# Frontend.net
KiCad netlist of a schematic drawn in Altium Designer
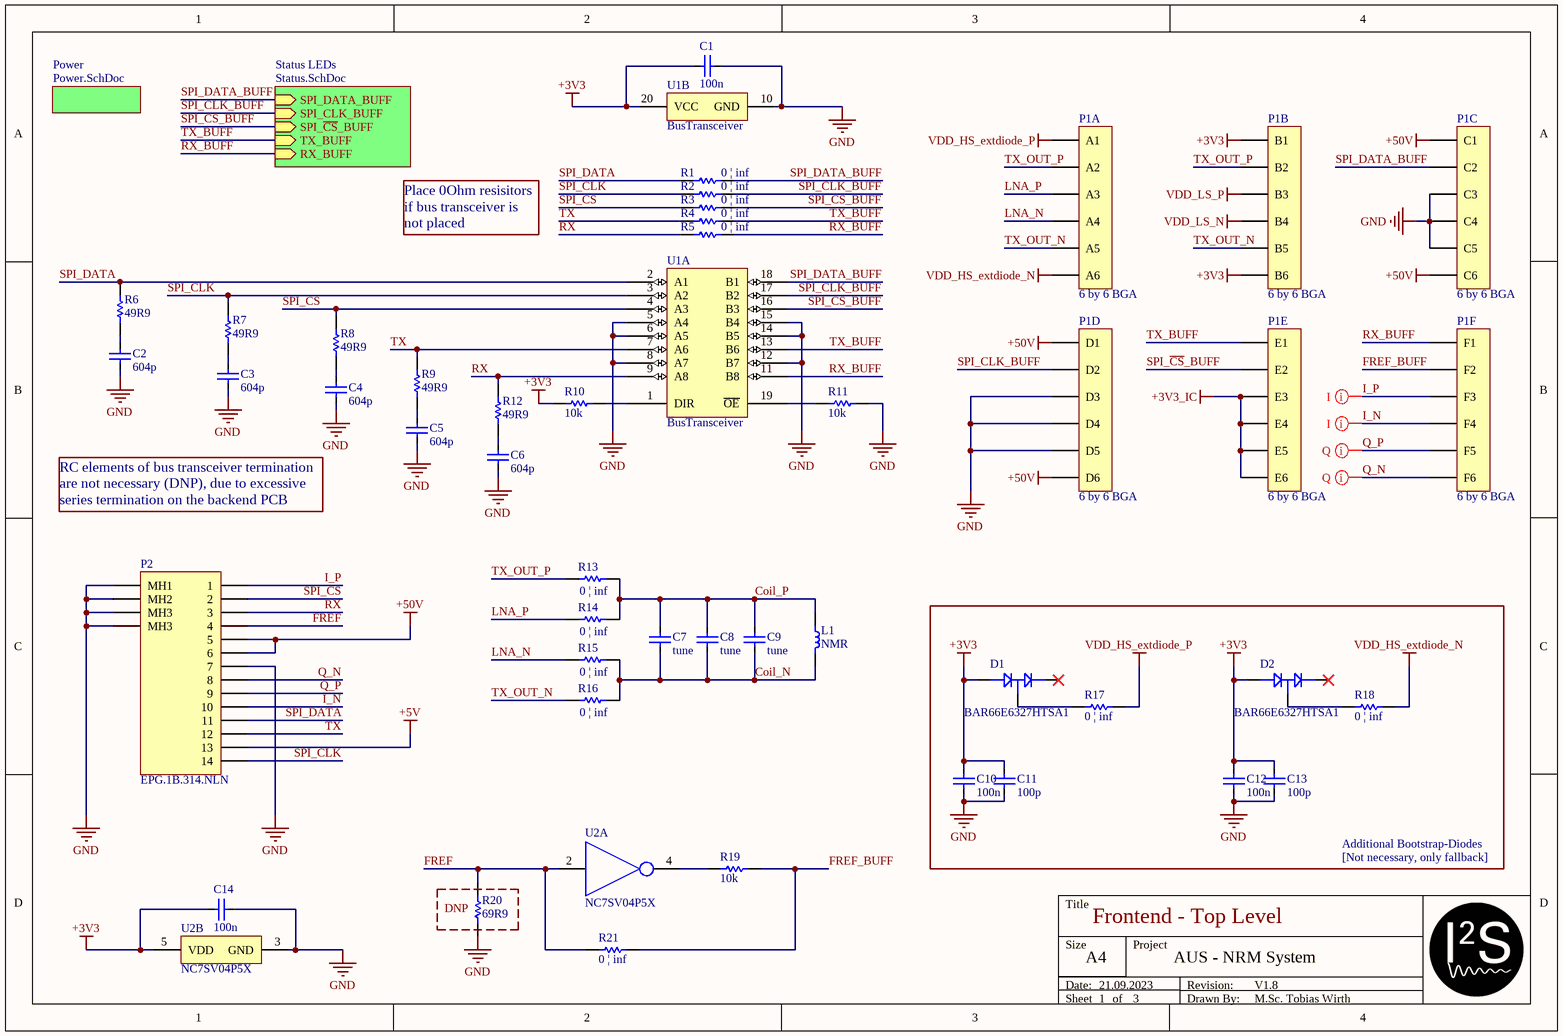
[diagram p0: Frontend.SchDoc]

(export (version "E")
  (design (tool "Eeschema 10.0.6"))
  (components
    (comp (ref "C1") (value "100n") (footprint "CAP_0402") (libsource (lib "IIS-Lib_TW") (part "Cap")))
    (comp (ref "C2") (value "604p") (footprint "CAP_0402") (libsource (lib "IIS-Lib_TW") (part "Cap")))
    (comp (ref "C3") (value "604p") (footprint "CAP_0402") (libsource (lib "IIS-Lib_TW") (part "Cap")))
    (comp (ref "C4") (value "604p") (footprint "CAP_0402") (libsource (lib "IIS-Lib_TW") (part "Cap")))
    (comp (ref "C5") (value "604p") (footprint "CAP_0402") (libsource (lib "IIS-Lib_TW") (part "Cap")))
    (comp (ref "C6") (value "604p") (footprint "CAP_0402") (libsource (lib "IIS-Lib_TW") (part "Cap")))
    (comp (ref "C7") (value "tune") (footprint "CAP_1206") (libsource (lib "IIS-Lib_TW") (part "Cap")))
    (comp (ref "C8") (value "tune") (footprint "CAP_0805") (libsource (lib "IIS-Lib_TW") (part "Cap")))
    (comp (ref "C9") (value "tune") (footprint "CAP_0603") (libsource (lib "IIS-Lib_TW") (part "Cap")))
    (comp (ref "C10") (value "100n") (footprint "CAP_0402") (libsource (lib "IIS-Lib_TW") (part "Cap")))
    (comp (ref "C11") (value "100p") (footprint "CAP_0402") (libsource (lib "IIS-Lib_TW") (part "Cap")))
    (comp (ref "C12") (value "100n") (footprint "CAP_0402") (libsource (lib "IIS-Lib_TW") (part "Cap")))
    (comp (ref "C13") (value "100p") (footprint "CAP_0402") (libsource (lib "IIS-Lib_TW") (part "Cap")))
    (comp (ref "C14") (value "100n") (footprint "CAP_0402") (libsource (lib "IIS-Lib_TW") (part "Cap")))
    (comp (ref "D1")
      (value "BAR66E6327HTSA1")
      (footprint "SOT23")
      (description "SMP1320-075LF (SC-70)\r\nBAV99 (SOT23)")
      (libsource (lib "IIS-Lib_TW") (part "Diode_series"))
    )
    (comp (ref "D2")
      (value "BAR66E6327HTSA1")
      (footprint "SOT23")
      (description "SMP1320-075LF (SC-70)\r\nBAV99 (SOT23)")
      (libsource (lib "IIS-Lib_TW") (part "Diode_series"))
    )
    (comp (ref "L1") (value "NMR") (footprint "NMR-Coil-Pads") (libsource (lib "IIS-Lib_TW") (part "Ind")))
    (comp (ref "P1")
      (value "6 by 6 BGA")
      (footprint "BGA36C230P6X6_1500X1500X190 - Interposer")
      (libsource (lib "IIS-Lib_TW") (part "BGA_6x6"))
    )
    (comp (ref "P2")
      (value "EPG.1B.314.NLN")
      (footprint "EPG.1B.314.NLN")
      (libsource (lib "IIS-Lib_TW") (part "EPG.1B.314.NLN"))
    )
    (comp (ref "R1") (value "0 ¦ inf") (footprint "RES_0402") (libsource (lib "IIS-Lib_TW") (part "Res")))
    (comp (ref "R2") (value "0 ¦ inf") (footprint "RES_0402") (libsource (lib "IIS-Lib_TW") (part "Res")))
    (comp (ref "R3") (value "0 ¦ inf") (footprint "RES_0402") (libsource (lib "IIS-Lib_TW") (part "Res")))
    (comp (ref "R4") (value "0 ¦ inf") (footprint "RES_0402") (libsource (lib "IIS-Lib_TW") (part "Res")))
    (comp (ref "R5") (value "0 ¦ inf") (footprint "RES_0402") (libsource (lib "IIS-Lib_TW") (part "Res")))
    (comp (ref "R6") (value "49R9") (footprint "RES_0402") (libsource (lib "IIS-Lib_TW") (part "Res")))
    (comp (ref "R7") (value "49R9") (footprint "RES_0402") (libsource (lib "IIS-Lib_TW") (part "Res")))
    (comp (ref "R8") (value "49R9") (footprint "RES_0402") (libsource (lib "IIS-Lib_TW") (part "Res")))
    (comp (ref "R9") (value "49R9") (footprint "RES_0402") (libsource (lib "IIS-Lib_TW") (part "Res")))
    (comp (ref "R10") (value "10k") (footprint "RES_0402") (libsource (lib "IIS-Lib_TW") (part "Res")))
    (comp (ref "R11") (value "10k") (footprint "RES_0402") (libsource (lib "IIS-Lib_TW") (part "Res")))
    (comp (ref "R12") (value "49R9") (footprint "RES_0402") (libsource (lib "IIS-Lib_TW") (part "Res")))
    (comp (ref "R13") (value "0 ¦ inf") (footprint "RES_0402") (libsource (lib "IIS-Lib_TW") (part "Res")))
    (comp (ref "R14") (value "0 ¦ inf") (footprint "RES_0402") (libsource (lib "IIS-Lib_TW") (part "Res")))
    (comp (ref "R15") (value "0 ¦ inf") (footprint "RES_0402") (libsource (lib "IIS-Lib_TW") (part "Res")))
    (comp (ref "R16") (value "0 ¦ inf") (footprint "RES_0402") (libsource (lib "IIS-Lib_TW") (part "Res")))
    (comp (ref "R17") (value "0 ¦ inf") (footprint "RES_0402") (libsource (lib "IIS-Lib_TW") (part "Res")))
    (comp (ref "R18") (value "0 ¦ inf") (footprint "RES_0402") (libsource (lib "IIS-Lib_TW") (part "Res")))
    (comp (ref "R19") (value "10k") (footprint "RES_0402") (libsource (lib "IIS-Lib_TW") (part "Res")))
    (comp (ref "R20") (value "69R9") (footprint "RES_0603") (libsource (lib "IIS-Lib_TW") (part "Res")))
    (comp (ref "R21") (value "0 ¦ inf") (footprint "RES_0402") (libsource (lib "IIS-Lib_TW") (part "Res")))
    (comp (ref "U1")
      (value "BusTransceiver")
      (footprint "TSSOP-20")
      (libsource (lib "") (part "74LVC245A_1"))
    )
    (comp (ref "U2")
      (value "NC7SV04P5X")
      (footprint "SOT23-65P210X110-5N")
      (libsource (lib "IIS-Lib_TW") (part "NC7SV04P5X"))
    )
  )
  (nets
    (net (code "1") (name "+3V3") (class "Default")
      (node (ref "C1") (pin "1") (pinfunction "1_1") (pintype "passive"))
      (node (ref "C10") (pin "1") (pinfunction "1_1") (pintype "passive"))
      (node (ref "C11") (pin "1") (pinfunction "1_1") (pintype "passive"))
      (node (ref "C12") (pin "1") (pinfunction "1_1") (pintype "passive"))
      (node (ref "C13") (pin "1") (pinfunction "1_1") (pintype "passive"))
      (node (ref "C14") (pin "1") (pinfunction "1_1") (pintype "passive"))
      (node (ref "D1") (pin "1") (pinfunction "1_1") (pintype "passive"))
      (node (ref "D2") (pin "1") (pinfunction "1_1") (pintype "passive"))
      (node (ref "P1") (pin "B1") (pinfunction "B1_B1") (pintype "passive"))
      (node (ref "P1") (pin "B6") (pinfunction "B6_B6") (pintype "passive"))
      (node (ref "R10") (pin "1") (pinfunction "1_1") (pintype "passive"))
      (node (ref "U1") (pin "20") (pinfunction "VCC_20") (pintype "passive"))
      (node (ref "U2") (pin "5") (pinfunction "VDD_5") (pintype "passive"))
    )
    (net (code "2") (name "+3V3_IC") (class "Default")
      (node (ref "P1") (pin "E3") (pinfunction "E3_E3") (pintype "passive"))
      (node (ref "P1") (pin "E4") (pinfunction "E4_E4") (pintype "passive"))
      (node (ref "P1") (pin "E5") (pinfunction "E5_E5") (pintype "passive"))
      (node (ref "P1") (pin "E6") (pinfunction "E6_E6") (pintype "passive"))
    )
    (net (code "3") (name "+5V") (class "Default")
      (node (ref "P2") (pin "13") (pinfunction "13_13") (pintype "passive"))
    )
    (net (code "4") (name "+50V") (class "Default")
      (node (ref "P1") (pin "C1") (pinfunction "C1_C1") (pintype "passive"))
      (node (ref "P1") (pin "C6") (pinfunction "C6_C6") (pintype "passive"))
      (node (ref "P1") (pin "D1") (pinfunction "D1_D1") (pintype "passive"))
      (node (ref "P1") (pin "D6") (pinfunction "D6_D6") (pintype "passive"))
      (node (ref "P2") (pin "5") (pinfunction "5_5") (pintype "passive"))
      (node (ref "P2") (pin "6") (pinfunction "6_6") (pintype "passive"))
    )
    (net (code "5") (name "/Coil_N") (class "Default")
      (node (ref "C7") (pin "2") (pinfunction "2_2") (pintype "passive"))
      (node (ref "C8") (pin "2") (pinfunction "2_2") (pintype "passive"))
      (node (ref "C9") (pin "2") (pinfunction "2_2") (pintype "passive"))
      (node (ref "L1") (pin "2") (pinfunction "2_2") (pintype "passive"))
      (node (ref "R15") (pin "1") (pinfunction "1_1") (pintype "passive"))
      (node (ref "R16") (pin "1") (pinfunction "1_1") (pintype "passive"))
    )
    (net (code "6") (name "/Coil_P") (class "Default")
      (node (ref "C7") (pin "1") (pinfunction "1_1") (pintype "passive"))
      (node (ref "C8") (pin "1") (pinfunction "1_1") (pintype "passive"))
      (node (ref "C9") (pin "1") (pinfunction "1_1") (pintype "passive"))
      (node (ref "L1") (pin "1") (pinfunction "1_1") (pintype "passive"))
      (node (ref "R13") (pin "1") (pinfunction "1_1") (pintype "passive"))
      (node (ref "R14") (pin "1") (pinfunction "1_1") (pintype "passive"))
    )
    (net (code "7") (name "/FREF") (class "Default")
      (node (ref "P2") (pin "4") (pinfunction "4_4") (pintype "passive"))
      (node (ref "R20") (pin "2") (pinfunction "2_2") (pintype "passive"))
      (node (ref "R21") (pin "2") (pinfunction "2_2") (pintype "passive"))
      (node (ref "U2") (pin "2") (pinfunction "2_2") (pintype "passive"))
    )
    (net (code "8") (name "/FREF_BUFF") (class "Default")
      (node (ref "P1") (pin "F2") (pinfunction "F2_F2") (pintype "passive"))
      (node (ref "R19") (pin "2") (pinfunction "2_2") (pintype "passive"))
      (node (ref "R21") (pin "1") (pinfunction "1_1") (pintype "passive"))
    )
    (net (code "9") (name "/I_N") (class "Default")
      (node (ref "P1") (pin "F4") (pinfunction "F4_F4") (pintype "passive"))
      (node (ref "P2") (pin "10") (pinfunction "10_10") (pintype "passive"))
    )
    (net (code "10") (name "/I_P") (class "Default")
      (node (ref "P1") (pin "F3") (pinfunction "F3_F3") (pintype "passive"))
      (node (ref "P2") (pin "1") (pinfunction "1_1") (pintype "passive"))
    )
    (net (code "11") (name "/LNA_N") (class "Default")
      (node (ref "P1") (pin "A4") (pinfunction "A4_A4") (pintype "passive"))
      (node (ref "R15") (pin "2") (pinfunction "2_2") (pintype "passive"))
    )
    (net (code "12") (name "/LNA_P") (class "Default")
      (node (ref "P1") (pin "A3") (pinfunction "A3_A3") (pintype "passive"))
      (node (ref "R14") (pin "2") (pinfunction "2_2") (pintype "passive"))
    )
    (net (code "13") (name "/Q_N") (class "Default")
      (node (ref "P1") (pin "F6") (pinfunction "F6_F6") (pintype "passive"))
      (node (ref "P2") (pin "8") (pinfunction "8_8") (pintype "passive"))
    )
    (net (code "14") (name "/Q_P") (class "Default")
      (node (ref "P1") (pin "F5") (pinfunction "F5_F5") (pintype "passive"))
      (node (ref "P2") (pin "9") (pinfunction "9_9") (pintype "passive"))
    )
    (net (code "15") (name "/RX") (class "Default")
      (node (ref "P2") (pin "3") (pinfunction "3_3") (pintype "passive"))
      (node (ref "R12") (pin "2") (pinfunction "2_2") (pintype "passive"))
      (node (ref "R5") (pin "1") (pinfunction "1_1") (pintype "passive"))
      (node (ref "U1") (pin "9") (pinfunction "A8_9") (pintype "bidirectional"))
    )
    (net (code "16") (name "/RX_BUFF") (class "Default")
      (node (ref "P1") (pin "F1") (pinfunction "F1_F1") (pintype "passive"))
      (node (ref "R5") (pin "2") (pinfunction "2_2") (pintype "passive"))
      (node (ref "U1") (pin "11") (pinfunction "B8_11") (pintype "bidirectional"))
    )
    (net (code "17") (name "/SPI_CLK") (class "Default")
      (node (ref "P2") (pin "14") (pinfunction "14_14") (pintype "passive"))
      (node (ref "R2") (pin "1") (pinfunction "1_1") (pintype "passive"))
      (node (ref "R7") (pin "2") (pinfunction "2_2") (pintype "passive"))
      (node (ref "U1") (pin "3") (pinfunction "A2_3") (pintype "bidirectional"))
    )
    (net (code "18") (name "/SPI_CLK_BUFF") (class "Default")
      (node (ref "P1") (pin "D2") (pinfunction "D2_D2") (pintype "passive"))
      (node (ref "R2") (pin "2") (pinfunction "2_2") (pintype "passive"))
      (node (ref "U1") (pin "17") (pinfunction "B2_17") (pintype "bidirectional"))
    )
    (net (code "19") (name "/SPI_DATA") (class "Default")
      (node (ref "P2") (pin "11") (pinfunction "11_11") (pintype "passive"))
      (node (ref "R1") (pin "1") (pinfunction "1_1") (pintype "passive"))
      (node (ref "R6") (pin "2") (pinfunction "2_2") (pintype "passive"))
      (node (ref "U1") (pin "2") (pinfunction "A1_2") (pintype "bidirectional"))
    )
    (net (code "20") (name "/SPI_DATA_BUFF") (class "Default")
      (node (ref "P1") (pin "C2") (pinfunction "C2_C2") (pintype "passive"))
      (node (ref "R1") (pin "2") (pinfunction "2_2") (pintype "passive"))
      (node (ref "U1") (pin "18") (pinfunction "B1_18") (pintype "bidirectional"))
    )
    (net (code "21") (name "/SPI_~{CS}") (class "Default")
      (node (ref "P2") (pin "2") (pinfunction "2_2") (pintype "passive"))
      (node (ref "R3") (pin "1") (pinfunction "1_1") (pintype "passive"))
      (node (ref "R8") (pin "2") (pinfunction "2_2") (pintype "passive"))
      (node (ref "U1") (pin "4") (pinfunction "A3_4") (pintype "bidirectional"))
    )
    (net (code "22") (name "/SPI_~{CS}_BUFF") (class "Default")
      (node (ref "P1") (pin "E2") (pinfunction "E2_E2") (pintype "passive"))
      (node (ref "R3") (pin "2") (pinfunction "2_2") (pintype "passive"))
      (node (ref "U1") (pin "16") (pinfunction "B3_16") (pintype "bidirectional"))
    )
    (net (code "23") (name "/TX") (class "Default")
      (node (ref "P2") (pin "12") (pinfunction "12_12") (pintype "passive"))
      (node (ref "R4") (pin "1") (pinfunction "1_1") (pintype "passive"))
      (node (ref "R9") (pin "2") (pinfunction "2_2") (pintype "passive"))
      (node (ref "U1") (pin "7") (pinfunction "A6_7") (pintype "bidirectional"))
    )
    (net (code "24") (name "/TX_BUFF") (class "Default")
      (node (ref "P1") (pin "E1") (pinfunction "E1_E1") (pintype "passive"))
      (node (ref "R4") (pin "2") (pinfunction "2_2") (pintype "passive"))
      (node (ref "U1") (pin "13") (pinfunction "B6_13") (pintype "bidirectional"))
    )
    (net (code "25") (name "/TX_OUT_N") (class "Default")
      (node (ref "P1") (pin "A5") (pinfunction "A5_A5") (pintype "passive"))
      (node (ref "P1") (pin "B5") (pinfunction "B5_B5") (pintype "passive"))
      (node (ref "R16") (pin "2") (pinfunction "2_2") (pintype "passive"))
    )
    (net (code "26") (name "/TX_OUT_P") (class "Default")
      (node (ref "P1") (pin "A2") (pinfunction "A2_A2") (pintype "passive"))
      (node (ref "P1") (pin "B2") (pinfunction "B2_B2") (pintype "passive"))
      (node (ref "R13") (pin "2") (pinfunction "2_2") (pintype "passive"))
    )
    (net (code "27") (name "GND") (class "Default")
      (node (ref "C1") (pin "2") (pinfunction "2_2") (pintype "passive"))
      (node (ref "C10") (pin "2") (pinfunction "2_2") (pintype "passive"))
      (node (ref "C11") (pin "2") (pinfunction "2_2") (pintype "passive"))
      (node (ref "C12") (pin "2") (pinfunction "2_2") (pintype "passive"))
      (node (ref "C13") (pin "2") (pinfunction "2_2") (pintype "passive"))
      (node (ref "C14") (pin "2") (pinfunction "2_2") (pintype "passive"))
      (node (ref "C2") (pin "2") (pinfunction "2_2") (pintype "passive"))
      (node (ref "C3") (pin "2") (pinfunction "2_2") (pintype "passive"))
      (node (ref "C4") (pin "2") (pinfunction "2_2") (pintype "passive"))
      (node (ref "C5") (pin "2") (pinfunction "2_2") (pintype "passive"))
      (node (ref "C6") (pin "2") (pinfunction "2_2") (pintype "passive"))
      (node (ref "P1") (pin "C3") (pinfunction "C3_C3") (pintype "passive"))
      (node (ref "P1") (pin "C4") (pinfunction "C4_C4") (pintype "passive"))
      (node (ref "P1") (pin "C5") (pinfunction "C5_C5") (pintype "passive"))
      (node (ref "P1") (pin "D3") (pinfunction "D3_D3") (pintype "passive"))
      (node (ref "P1") (pin "D4") (pinfunction "D4_D4") (pintype "passive"))
      (node (ref "P1") (pin "D5") (pinfunction "D5_D5") (pintype "passive"))
      (node (ref "P2") (pin "15") (pinfunction "MH1_15") (pintype "passive"))
      (node (ref "P2") (pin "16") (pinfunction "MH2_16") (pintype "passive"))
      (node (ref "P2") (pin "17") (pinfunction "MH3_17") (pintype "passive"))
      (node (ref "P2") (pin "18") (pinfunction "MH3_18") (pintype "passive"))
      (node (ref "P2") (pin "7") (pinfunction "7_7") (pintype "passive"))
      (node (ref "R11") (pin "2") (pinfunction "2_2") (pintype "passive"))
      (node (ref "R20") (pin "1") (pinfunction "1_1") (pintype "passive"))
      (node (ref "U1") (pin "10") (pinfunction "GND_10") (pintype "passive"))
      (node (ref "U1") (pin "12") (pinfunction "B7_12") (pintype "bidirectional"))
      (node (ref "U1") (pin "14") (pinfunction "B5_14") (pintype "bidirectional"))
      (node (ref "U1") (pin "15") (pinfunction "B4_15") (pintype "bidirectional"))
      (node (ref "U1") (pin "5") (pinfunction "A4_5") (pintype "bidirectional"))
      (node (ref "U1") (pin "6") (pinfunction "A5_6") (pintype "bidirectional"))
      (node (ref "U1") (pin "8") (pinfunction "A7_8") (pintype "bidirectional"))
      (node (ref "U2") (pin "3") (pinfunction "GND_3") (pintype "passive"))
    )
    (net (code "28") (name "Net-(C2-Pad1)") (class "Default")
      (node (ref "C2") (pin "1") (pinfunction "1_1") (pintype "passive"))
      (node (ref "R6") (pin "1") (pinfunction "1_1") (pintype "passive"))
    )
    (net (code "29") (name "Net-(C3-Pad1)") (class "Default")
      (node (ref "C3") (pin "1") (pinfunction "1_1") (pintype "passive"))
      (node (ref "R7") (pin "1") (pinfunction "1_1") (pintype "passive"))
    )
    (net (code "30") (name "Net-(C4-Pad1)") (class "Default")
      (node (ref "C4") (pin "1") (pinfunction "1_1") (pintype "passive"))
      (node (ref "R8") (pin "1") (pinfunction "1_1") (pintype "passive"))
    )
    (net (code "31") (name "Net-(C5-Pad1)") (class "Default")
      (node (ref "C5") (pin "1") (pinfunction "1_1") (pintype "passive"))
      (node (ref "R9") (pin "1") (pinfunction "1_1") (pintype "passive"))
    )
    (net (code "32") (name "Net-(C6-Pad1)") (class "Default")
      (node (ref "C6") (pin "1") (pinfunction "1_1") (pintype "passive"))
      (node (ref "R12") (pin "1") (pinfunction "1_1") (pintype "passive"))
    )
    (net (code "33") (name "Net-(D1-Pad3)") (class "Default")
      (node (ref "D1") (pin "3") (pinfunction "3_3") (pintype "passive"))
      (node (ref "R17") (pin "2") (pinfunction "2_2") (pintype "passive"))
    )
    (net (code "34") (name "Net-(D2-Pad3)") (class "Default")
      (node (ref "D2") (pin "3") (pinfunction "3_3") (pintype "passive"))
      (node (ref "R18") (pin "2") (pinfunction "2_2") (pintype "passive"))
    )
    (net (code "35") (name "Net-(R19-Pad1)") (class "Default")
      (node (ref "R19") (pin "1") (pinfunction "1_1") (pintype "passive"))
      (node (ref "U2") (pin "4") (pinfunction "4_4") (pintype "passive"))
    )
    (net (code "36") (name "Net-(U1A-DIR)") (class "Default")
      (node (ref "R10") (pin "2") (pinfunction "2_2") (pintype "passive"))
      (node (ref "U1") (pin "1") (pinfunction "DIR_1") (pintype "passive"))
    )
    (net (code "37") (name "Net-(U1A-~{OE})") (class "Default")
      (node (ref "R11") (pin "1") (pinfunction "1_1") (pintype "passive"))
      (node (ref "U1") (pin "19") (pinfunction "~{OE}_19") (pintype "passive"))
    )
    (net (code "38") (name "VDD_HS_extdiode_N") (class "Default")
      (node (ref "P1") (pin "A6") (pinfunction "A6_A6") (pintype "passive"))
      (node (ref "R18") (pin "1") (pinfunction "1_1") (pintype "passive"))
    )
    (net (code "39") (name "VDD_HS_extdiode_P") (class "Default")
      (node (ref "P1") (pin "A1") (pinfunction "A1_A1") (pintype "passive"))
      (node (ref "R17") (pin "1") (pinfunction "1_1") (pintype "passive"))
    )
    (net (code "40") (name "VDD_LS_N") (class "Default")
      (node (ref "P1") (pin "B4") (pinfunction "B4_B4") (pintype "passive"))
    )
    (net (code "41") (name "VDD_LS_P") (class "Default")
      (node (ref "P1") (pin "B3") (pinfunction "B3_B3") (pintype "passive"))
    )
    (net (code "42") (name "unconnected-(D1-Pad2)") (class "Default")
      (node (ref "D1") (pin "2") (pinfunction "2_2") (pintype "passive+no_connect"))
    )
    (net (code "43") (name "unconnected-(D2-Pad2)") (class "Default")
      (node (ref "D2") (pin "2") (pinfunction "2_2") (pintype "passive+no_connect"))
    )
  )
)
